# CW342_FPGA_PWR.net
KiCad netlist of a schematic drawn in Altium Designer
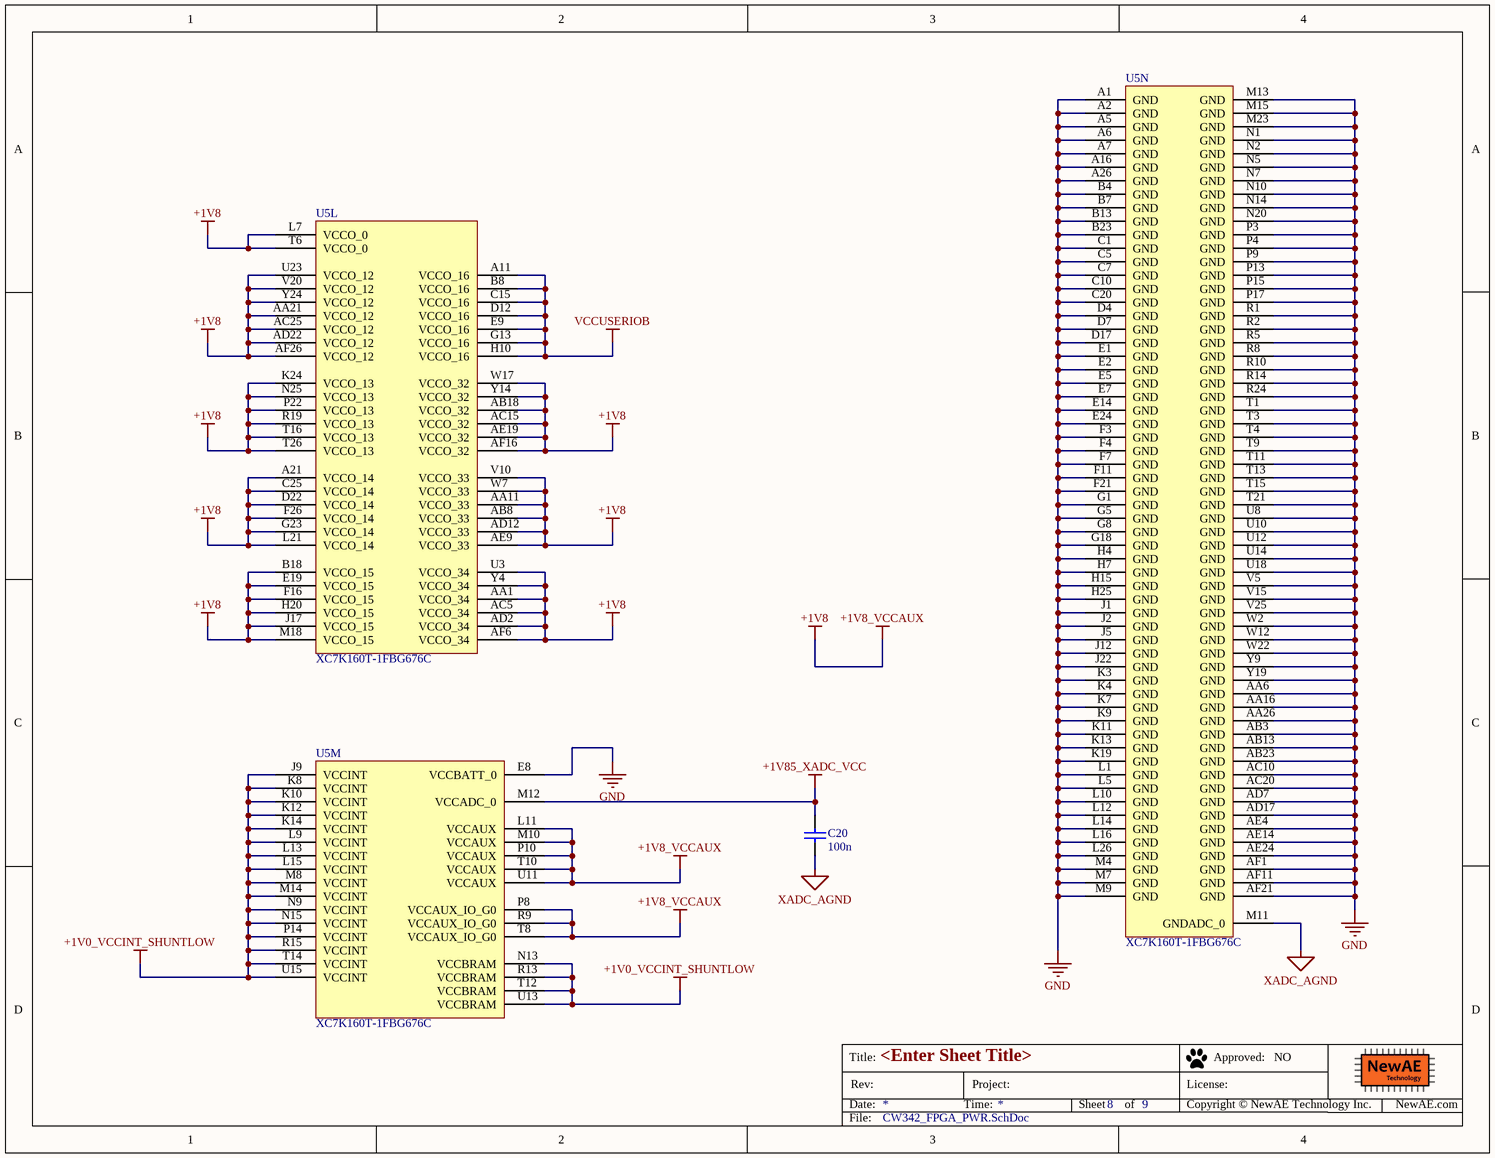
[diagram p0: CW342_FPGA_PWR.SchDoc]

(export (version "E")
  (design (tool "Eeschema 10.0.6"))
  (components
    (comp (ref "C20")
      (value "100n")
      (footprint "CAPC0402_M")
      (description "100n, 0402")
      (fields (field (name "PART NUMBER") "CCHIP-100n-0402"))
      (libsource (lib "NewAE_AltiumLib") (part "CAP"))
    )
    (comp (ref "U5")
      (value "XC7K160T-1FBG676C")
      (footprint "FBG676")
      (description "Kintex-7 FPGA, 400 User I/Os, 8 GTX, 676-Ball BGA, Speed Grade 1, Commercial Grade, Pb-Free")
      (fields (field (name "GENERIC PART NUMBER") "XC7K160T") (field (name "MANUFACTURER") "Xilinx"))
      (libsource (lib "Altium Content Vault") (part "XNLX-XC7K160T-XNLX-FBG676"))
    )
  )
  (nets
    (net (code "1") (name "+1V0_VCCINT_SHUNTLOW") (class "Default")
      (node (ref "U5") (pin "J9") (pinfunction "VCCINT_J9") (pintype "power_in"))
      (node (ref "U5") (pin "K10") (pinfunction "VCCINT_K10") (pintype "power_in"))
      (node (ref "U5") (pin "K12") (pinfunction "VCCINT_K12") (pintype "power_in"))
      (node (ref "U5") (pin "K14") (pinfunction "VCCINT_K14") (pintype "power_in"))
      (node (ref "U5") (pin "K8") (pinfunction "VCCINT_K8") (pintype "power_in"))
      (node (ref "U5") (pin "L13") (pinfunction "VCCINT_L13") (pintype "power_in"))
      (node (ref "U5") (pin "L15") (pinfunction "VCCINT_L15") (pintype "power_in"))
      (node (ref "U5") (pin "L9") (pinfunction "VCCINT_L9") (pintype "power_in"))
      (node (ref "U5") (pin "M14") (pinfunction "VCCINT_M14") (pintype "power_in"))
      (node (ref "U5") (pin "M8") (pinfunction "VCCINT_M8") (pintype "power_in"))
      (node (ref "U5") (pin "N13") (pinfunction "VCCBRAM_N13") (pintype "power_in"))
      (node (ref "U5") (pin "N15") (pinfunction "VCCINT_N15") (pintype "power_in"))
      (node (ref "U5") (pin "N9") (pinfunction "VCCINT_N9") (pintype "power_in"))
      (node (ref "U5") (pin "P14") (pinfunction "VCCINT_P14") (pintype "power_in"))
      (node (ref "U5") (pin "R13") (pinfunction "VCCBRAM_R13") (pintype "power_in"))
      (node (ref "U5") (pin "R15") (pinfunction "VCCINT_R15") (pintype "power_in"))
      (node (ref "U5") (pin "T12") (pinfunction "VCCBRAM_T12") (pintype "power_in"))
      (node (ref "U5") (pin "T14") (pinfunction "VCCINT_T14") (pintype "power_in"))
      (node (ref "U5") (pin "U13") (pinfunction "VCCBRAM_U13") (pintype "power_in"))
      (node (ref "U5") (pin "U15") (pinfunction "VCCINT_U15") (pintype "power_in"))
    )
    (net (code "2") (name "+1V8") (class "Default")
      (node (ref "U5") (pin "A21") (pinfunction "VCCO_14_A21") (pintype "power_in"))
      (node (ref "U5") (pin "AA1") (pinfunction "VCCO_34_AA1") (pintype "power_in"))
      (node (ref "U5") (pin "AA11") (pinfunction "VCCO_33_AA11") (pintype "power_in"))
      (node (ref "U5") (pin "AA21") (pinfunction "VCCO_12_AA21") (pintype "power_in"))
      (node (ref "U5") (pin "AB18") (pinfunction "VCCO_32_AB18") (pintype "power_in"))
      (node (ref "U5") (pin "AB8") (pinfunction "VCCO_33_AB8") (pintype "power_in"))
      (node (ref "U5") (pin "AC15") (pinfunction "VCCO_32_AC15") (pintype "power_in"))
      (node (ref "U5") (pin "AC25") (pinfunction "VCCO_12_AC25") (pintype "power_in"))
      (node (ref "U5") (pin "AC5") (pinfunction "VCCO_34_AC5") (pintype "power_in"))
      (node (ref "U5") (pin "AD12") (pinfunction "VCCO_33_AD12") (pintype "power_in"))
      (node (ref "U5") (pin "AD2") (pinfunction "VCCO_34_AD2") (pintype "power_in"))
      (node (ref "U5") (pin "AD22") (pinfunction "VCCO_12_AD22") (pintype "power_in"))
      (node (ref "U5") (pin "AE19") (pinfunction "VCCO_32_AE19") (pintype "power_in"))
      (node (ref "U5") (pin "AE9") (pinfunction "VCCO_33_AE9") (pintype "power_in"))
      (node (ref "U5") (pin "AF16") (pinfunction "VCCO_32_AF16") (pintype "power_in"))
      (node (ref "U5") (pin "AF26") (pinfunction "VCCO_12_AF26") (pintype "power_in"))
      (node (ref "U5") (pin "AF6") (pinfunction "VCCO_34_AF6") (pintype "power_in"))
      (node (ref "U5") (pin "B18") (pinfunction "VCCO_15_B18") (pintype "power_in"))
      (node (ref "U5") (pin "C25") (pinfunction "VCCO_14_C25") (pintype "power_in"))
      (node (ref "U5") (pin "D22") (pinfunction "VCCO_14_D22") (pintype "power_in"))
      (node (ref "U5") (pin "E19") (pinfunction "VCCO_15_E19") (pintype "power_in"))
      (node (ref "U5") (pin "F16") (pinfunction "VCCO_15_F16") (pintype "power_in"))
      (node (ref "U5") (pin "F26") (pinfunction "VCCO_14_F26") (pintype "power_in"))
      (node (ref "U5") (pin "G23") (pinfunction "VCCO_14_G23") (pintype "power_in"))
      (node (ref "U5") (pin "H20") (pinfunction "VCCO_15_H20") (pintype "power_in"))
      (node (ref "U5") (pin "J17") (pinfunction "VCCO_15_J17") (pintype "power_in"))
      (node (ref "U5") (pin "K24") (pinfunction "VCCO_13_K24") (pintype "power_in"))
      (node (ref "U5") (pin "L11") (pinfunction "VCCAUX_L11") (pintype "power_in"))
      (node (ref "U5") (pin "L21") (pinfunction "VCCO_14_L21") (pintype "power_in"))
      (node (ref "U5") (pin "L7") (pinfunction "VCCO_0_L7") (pintype "power_in"))
      (node (ref "U5") (pin "M10") (pinfunction "VCCAUX_M10") (pintype "power_in"))
      (node (ref "U5") (pin "M18") (pinfunction "VCCO_15_M18") (pintype "power_in"))
      (node (ref "U5") (pin "N25") (pinfunction "VCCO_13_N25") (pintype "power_in"))
      (node (ref "U5") (pin "P10") (pinfunction "VCCAUX_P10") (pintype "power_in"))
      (node (ref "U5") (pin "P22") (pinfunction "VCCO_13_P22") (pintype "power_in"))
      (node (ref "U5") (pin "P8") (pinfunction "VCCAUX_IO_G0_P8") (pintype "power_in"))
      (node (ref "U5") (pin "R19") (pinfunction "VCCO_13_R19") (pintype "power_in"))
      (node (ref "U5") (pin "R9") (pinfunction "VCCAUX_IO_G0_R9") (pintype "power_in"))
      (node (ref "U5") (pin "T10") (pinfunction "VCCAUX_T10") (pintype "power_in"))
      (node (ref "U5") (pin "T16") (pinfunction "VCCO_13_T16") (pintype "power_in"))
      (node (ref "U5") (pin "T26") (pinfunction "VCCO_13_T26") (pintype "power_in"))
      (node (ref "U5") (pin "T6") (pinfunction "VCCO_0_T6") (pintype "power_in"))
      (node (ref "U5") (pin "T8") (pinfunction "VCCAUX_IO_G0_T8") (pintype "power_in"))
      (node (ref "U5") (pin "U11") (pinfunction "VCCAUX_U11") (pintype "power_in"))
      (node (ref "U5") (pin "U23") (pinfunction "VCCO_12_U23") (pintype "power_in"))
      (node (ref "U5") (pin "U3") (pinfunction "VCCO_34_U3") (pintype "power_in"))
      (node (ref "U5") (pin "V10") (pinfunction "VCCO_33_V10") (pintype "power_in"))
      (node (ref "U5") (pin "V20") (pinfunction "VCCO_12_V20") (pintype "power_in"))
      (node (ref "U5") (pin "W17") (pinfunction "VCCO_32_W17") (pintype "power_in"))
      (node (ref "U5") (pin "W7") (pinfunction "VCCO_33_W7") (pintype "power_in"))
      (node (ref "U5") (pin "Y14") (pinfunction "VCCO_32_Y14") (pintype "power_in"))
      (node (ref "U5") (pin "Y24") (pinfunction "VCCO_12_Y24") (pintype "power_in"))
      (node (ref "U5") (pin "Y4") (pinfunction "VCCO_34_Y4") (pintype "power_in"))
    )
    (net (code "3") (name "+1V85_XADC_VCC") (class "Default")
      (node (ref "C20") (pin "1") (pinfunction "1_1") (pintype "passive"))
      (node (ref "U5") (pin "M12") (pinfunction "VCCADC_0_M12") (pintype "power_in"))
    )
    (net (code "4") (name "GND") (class "Default")
      (node (ref "U5") (pin "A1") (pinfunction "GND_A1") (pintype "power_in"))
      (node (ref "U5") (pin "A16") (pinfunction "GND_A16") (pintype "power_in"))
      (node (ref "U5") (pin "A2") (pinfunction "GND_A2") (pintype "power_in"))
      (node (ref "U5") (pin "A26") (pinfunction "GND_A26") (pintype "power_in"))
      (node (ref "U5") (pin "A5") (pinfunction "GND_A5") (pintype "power_in"))
      (node (ref "U5") (pin "A6") (pinfunction "GND_A6") (pintype "power_in"))
      (node (ref "U5") (pin "A7") (pinfunction "GND_A7") (pintype "power_in"))
      (node (ref "U5") (pin "AA16") (pinfunction "GND_AA16") (pintype "power_in"))
      (node (ref "U5") (pin "AA26") (pinfunction "GND_AA26") (pintype "power_in"))
      (node (ref "U5") (pin "AA6") (pinfunction "GND_AA6") (pintype "power_in"))
      (node (ref "U5") (pin "AB13") (pinfunction "GND_AB13") (pintype "power_in"))
      (node (ref "U5") (pin "AB23") (pinfunction "GND_AB23") (pintype "power_in"))
      (node (ref "U5") (pin "AB3") (pinfunction "GND_AB3") (pintype "power_in"))
      (node (ref "U5") (pin "AC10") (pinfunction "GND_AC10") (pintype "power_in"))
      (node (ref "U5") (pin "AC20") (pinfunction "GND_AC20") (pintype "power_in"))
      (node (ref "U5") (pin "AD17") (pinfunction "GND_AD17") (pintype "power_in"))
      (node (ref "U5") (pin "AD7") (pinfunction "GND_AD7") (pintype "power_in"))
      (node (ref "U5") (pin "AE14") (pinfunction "GND_AE14") (pintype "power_in"))
      (node (ref "U5") (pin "AE24") (pinfunction "GND_AE24") (pintype "power_in"))
      (node (ref "U5") (pin "AE4") (pinfunction "GND_AE4") (pintype "power_in"))
      (node (ref "U5") (pin "AF1") (pinfunction "GND_AF1") (pintype "power_in"))
      (node (ref "U5") (pin "AF11") (pinfunction "GND_AF11") (pintype "power_in"))
      (node (ref "U5") (pin "AF21") (pinfunction "GND_AF21") (pintype "power_in"))
      (node (ref "U5") (pin "B13") (pinfunction "GND_B13") (pintype "power_in"))
      (node (ref "U5") (pin "B23") (pinfunction "GND_B23") (pintype "power_in"))
      (node (ref "U5") (pin "B4") (pinfunction "GND_B4") (pintype "power_in"))
      (node (ref "U5") (pin "B7") (pinfunction "GND_B7") (pintype "power_in"))
      (node (ref "U5") (pin "C1") (pinfunction "GND_C1") (pintype "power_in"))
      (node (ref "U5") (pin "C10") (pinfunction "GND_C10") (pintype "power_in"))
      (node (ref "U5") (pin "C20") (pinfunction "GND_C20") (pintype "power_in"))
      (node (ref "U5") (pin "C5") (pinfunction "GND_C5") (pintype "power_in"))
      (node (ref "U5") (pin "C7") (pinfunction "GND_C7") (pintype "power_in"))
      (node (ref "U5") (pin "D17") (pinfunction "GND_D17") (pintype "power_in"))
      (node (ref "U5") (pin "D4") (pinfunction "GND_D4") (pintype "power_in"))
      (node (ref "U5") (pin "D7") (pinfunction "GND_D7") (pintype "power_in"))
      (node (ref "U5") (pin "E1") (pinfunction "GND_E1") (pintype "power_in"))
      (node (ref "U5") (pin "E14") (pinfunction "GND_E14") (pintype "power_in"))
      (node (ref "U5") (pin "E2") (pinfunction "GND_E2") (pintype "power_in"))
      (node (ref "U5") (pin "E24") (pinfunction "GND_E24") (pintype "power_in"))
      (node (ref "U5") (pin "E5") (pinfunction "GND_E5") (pintype "power_in"))
      (node (ref "U5") (pin "E7") (pinfunction "GND_E7") (pintype "power_in"))
      (node (ref "U5") (pin "E8") (pinfunction "VCCBATT_0_E8") (pintype "power_in"))
      (node (ref "U5") (pin "F11") (pinfunction "GND_F11") (pintype "power_in"))
      (node (ref "U5") (pin "F21") (pinfunction "GND_F21") (pintype "power_in"))
      (node (ref "U5") (pin "F3") (pinfunction "GND_F3") (pintype "power_in"))
      (node (ref "U5") (pin "F4") (pinfunction "GND_F4") (pintype "power_in"))
      (node (ref "U5") (pin "F7") (pinfunction "GND_F7") (pintype "power_in"))
      (node (ref "U5") (pin "G1") (pinfunction "GND_G1") (pintype "power_in"))
      (node (ref "U5") (pin "G18") (pinfunction "GND_G18") (pintype "power_in"))
      (node (ref "U5") (pin "G5") (pinfunction "GND_G5") (pintype "power_in"))
      (node (ref "U5") (pin "G8") (pinfunction "GND_G8") (pintype "power_in"))
      (node (ref "U5") (pin "H15") (pinfunction "GND_H15") (pintype "power_in"))
      (node (ref "U5") (pin "H25") (pinfunction "GND_H25") (pintype "power_in"))
      (node (ref "U5") (pin "H4") (pinfunction "GND_H4") (pintype "power_in"))
      (node (ref "U5") (pin "H7") (pinfunction "GND_H7") (pintype "power_in"))
      (node (ref "U5") (pin "J1") (pinfunction "GND_J1") (pintype "power_in"))
      (node (ref "U5") (pin "J12") (pinfunction "GND_J12") (pintype "power_in"))
      (node (ref "U5") (pin "J2") (pinfunction "GND_J2") (pintype "power_in"))
      (node (ref "U5") (pin "J22") (pinfunction "GND_J22") (pintype "power_in"))
      (node (ref "U5") (pin "J5") (pinfunction "GND_J5") (pintype "power_in"))
      (node (ref "U5") (pin "K11") (pinfunction "GND_K11") (pintype "power_in"))
      (node (ref "U5") (pin "K13") (pinfunction "GND_K13") (pintype "power_in"))
      (node (ref "U5") (pin "K19") (pinfunction "GND_K19") (pintype "power_in"))
      (node (ref "U5") (pin "K3") (pinfunction "GND_K3") (pintype "power_in"))
      (node (ref "U5") (pin "K4") (pinfunction "GND_K4") (pintype "power_in"))
      (node (ref "U5") (pin "K7") (pinfunction "GND_K7") (pintype "power_in"))
      (node (ref "U5") (pin "K9") (pinfunction "GND_K9") (pintype "power_in"))
      (node (ref "U5") (pin "L1") (pinfunction "GND_L1") (pintype "power_in"))
      (node (ref "U5") (pin "L10") (pinfunction "GND_L10") (pintype "power_in"))
      (node (ref "U5") (pin "L12") (pinfunction "GND_L12") (pintype "power_in"))
      (node (ref "U5") (pin "L14") (pinfunction "GND_L14") (pintype "power_in"))
      (node (ref "U5") (pin "L16") (pinfunction "GND_L16") (pintype "power_in"))
      (node (ref "U5") (pin "L26") (pinfunction "GND_L26") (pintype "power_in"))
      (node (ref "U5") (pin "L5") (pinfunction "GND_L5") (pintype "power_in"))
      (node (ref "U5") (pin "M13") (pinfunction "GND_M13") (pintype "power_in"))
      (node (ref "U5") (pin "M15") (pinfunction "GND_M15") (pintype "power_in"))
      (node (ref "U5") (pin "M23") (pinfunction "GND_M23") (pintype "power_in"))
      (node (ref "U5") (pin "M4") (pinfunction "GND_M4") (pintype "power_in"))
      (node (ref "U5") (pin "M7") (pinfunction "GND_M7") (pintype "power_in"))
      (node (ref "U5") (pin "M9") (pinfunction "GND_M9") (pintype "power_in"))
      (node (ref "U5") (pin "N1") (pinfunction "GND_N1") (pintype "power_in"))
      (node (ref "U5") (pin "N10") (pinfunction "GND_N10") (pintype "power_in"))
      (node (ref "U5") (pin "N14") (pinfunction "GND_N14") (pintype "power_in"))
      (node (ref "U5") (pin "N2") (pinfunction "GND_N2") (pintype "power_in"))
      (node (ref "U5") (pin "N20") (pinfunction "GND_N20") (pintype "power_in"))
      (node (ref "U5") (pin "N5") (pinfunction "GND_N5") (pintype "power_in"))
      (node (ref "U5") (pin "N7") (pinfunction "GND_N7") (pintype "power_in"))
      (node (ref "U5") (pin "P13") (pinfunction "GND_P13") (pintype "power_in"))
      (node (ref "U5") (pin "P15") (pinfunction "GND_P15") (pintype "power_in"))
      (node (ref "U5") (pin "P17") (pinfunction "GND_P17") (pintype "power_in"))
      (node (ref "U5") (pin "P3") (pinfunction "GND_P3") (pintype "power_in"))
      (node (ref "U5") (pin "P4") (pinfunction "GND_P4") (pintype "power_in"))
      (node (ref "U5") (pin "P9") (pinfunction "GND_P9") (pintype "power_in"))
      (node (ref "U5") (pin "R1") (pinfunction "GND_R1") (pintype "power_in"))
      (node (ref "U5") (pin "R10") (pinfunction "GND_R10") (pintype "power_in"))
      (node (ref "U5") (pin "R14") (pinfunction "GND_R14") (pintype "power_in"))
      (node (ref "U5") (pin "R2") (pinfunction "GND_R2") (pintype "power_in"))
      (node (ref "U5") (pin "R24") (pinfunction "GND_R24") (pintype "power_in"))
      (node (ref "U5") (pin "R5") (pinfunction "GND_R5") (pintype "power_in"))
      (node (ref "U5") (pin "R8") (pinfunction "GND_R8") (pintype "power_in"))
      (node (ref "U5") (pin "T1") (pinfunction "GND_T1") (pintype "power_in"))
      (node (ref "U5") (pin "T11") (pinfunction "GND_T11") (pintype "power_in"))
      (node (ref "U5") (pin "T13") (pinfunction "GND_T13") (pintype "power_in"))
      (node (ref "U5") (pin "T15") (pinfunction "GND_T15") (pintype "power_in"))
      (node (ref "U5") (pin "T21") (pinfunction "GND_T21") (pintype "power_in"))
      (node (ref "U5") (pin "T3") (pinfunction "GND_T3") (pintype "power_in"))
      (node (ref "U5") (pin "T4") (pinfunction "GND_T4") (pintype "power_in"))
      (node (ref "U5") (pin "T9") (pinfunction "GND_T9") (pintype "power_in"))
      (node (ref "U5") (pin "U10") (pinfunction "GND_U10") (pintype "power_in"))
      (node (ref "U5") (pin "U12") (pinfunction "GND_U12") (pintype "power_in"))
      (node (ref "U5") (pin "U14") (pinfunction "GND_U14") (pintype "power_in"))
      (node (ref "U5") (pin "U18") (pinfunction "GND_U18") (pintype "power_in"))
      (node (ref "U5") (pin "U8") (pinfunction "GND_U8") (pintype "power_in"))
      (node (ref "U5") (pin "V15") (pinfunction "GND_V15") (pintype "power_in"))
      (node (ref "U5") (pin "V25") (pinfunction "GND_V25") (pintype "power_in"))
      (node (ref "U5") (pin "V5") (pinfunction "GND_V5") (pintype "power_in"))
      (node (ref "U5") (pin "W12") (pinfunction "GND_W12") (pintype "power_in"))
      (node (ref "U5") (pin "W2") (pinfunction "GND_W2") (pintype "power_in"))
      (node (ref "U5") (pin "W22") (pinfunction "GND_W22") (pintype "power_in"))
      (node (ref "U5") (pin "Y19") (pinfunction "GND_Y19") (pintype "power_in"))
      (node (ref "U5") (pin "Y9") (pinfunction "GND_Y9") (pintype "power_in"))
    )
    (net (code "5") (name "VCCUSERIOB") (class "Default")
      (node (ref "U5") (pin "A11") (pinfunction "VCCO_16_A11") (pintype "power_in"))
      (node (ref "U5") (pin "B8") (pinfunction "VCCO_16_B8") (pintype "power_in"))
      (node (ref "U5") (pin "C15") (pinfunction "VCCO_16_C15") (pintype "power_in"))
      (node (ref "U5") (pin "D12") (pinfunction "VCCO_16_D12") (pintype "power_in"))
      (node (ref "U5") (pin "E9") (pinfunction "VCCO_16_E9") (pintype "power_in"))
      (node (ref "U5") (pin "G13") (pinfunction "VCCO_16_G13") (pintype "power_in"))
      (node (ref "U5") (pin "H10") (pinfunction "VCCO_16_H10") (pintype "power_in"))
    )
    (net (code "6") (name "XADC_AGND") (class "Default")
      (node (ref "C20") (pin "2") (pinfunction "2_2") (pintype "passive"))
      (node (ref "U5") (pin "M11") (pinfunction "GNDADC_0_M11") (pintype "power_in"))
    )
  )
)
